# OpenSourceLights_v17.net
KiCad netlist of a schematic drawn in EAGLE
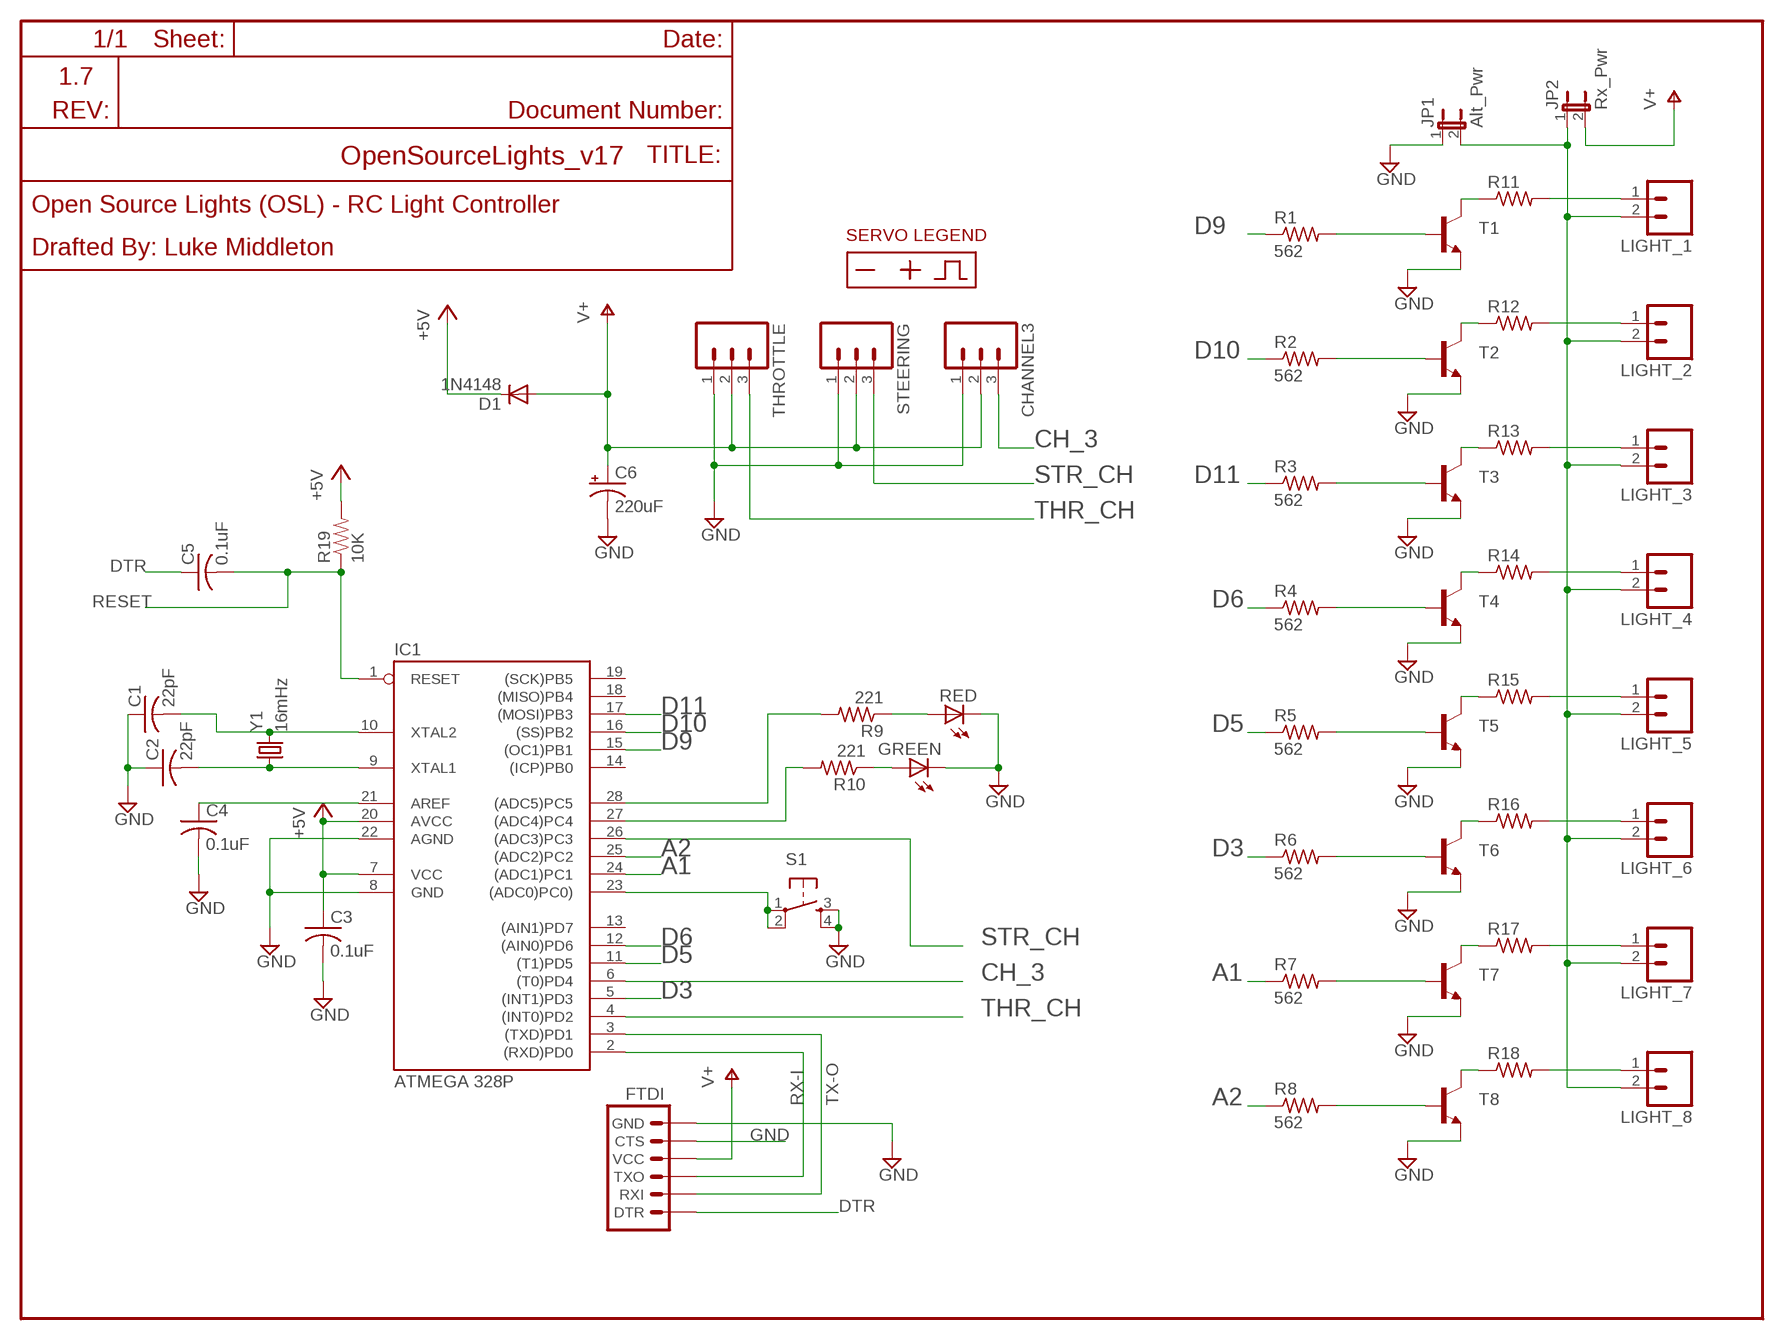
[diagram p0: schematic, sheet 1]

(export (version "E")
  (design (tool "Eeschema 10.0.6"))
  (components
    (comp (ref "C1")
      (value "22pF")
      (footprint "eagle-import:C025-025X050")
      (libsource (lib "eagle-import") (part "CAPACITORSMALL_THROUGH_HOLE"))
    )
    (comp (ref "C2")
      (value "22pF")
      (footprint "eagle-import:C025-025X050")
      (libsource (lib "eagle-import") (part "CAPACITORSMALL_THROUGH_HOLE"))
    )
    (comp (ref "C3")
      (value "0.1uF")
      (footprint "eagle-import:C025-025X050")
      (libsource (lib "eagle-import") (part "CAPACITORSMALL_THROUGH_HOLE"))
    )
    (comp (ref "C4")
      (value "0.1uF")
      (footprint "eagle-import:C025-025X050")
      (libsource (lib "eagle-import") (part "CAPACITORSMALL_THROUGH_HOLE"))
    )
    (comp (ref "C5")
      (value "0.1uF")
      (footprint "eagle-import:C025-025X050")
      (libsource (lib "eagle-import") (part "CAPACITORSMALL_THROUGH_HOLE"))
    )
    (comp (ref "C6")
      (value "220uF")
      (footprint "eagle-import:E5-10,5")
      (libsource (lib "eagle-import") (part "CPOL-USE5-10.5"))
    )
    (comp (ref "CHANNEL3")
      (value "M03LOCK")
      (footprint "eagle-import:1X03_LOCK")
      (libsource (lib "eagle-import") (part "M03LOCK"))
    )
    (comp (ref "D1")
      (value "1N4148")
      (footprint "eagle-import:DO35-10")
      (libsource (lib "eagle-import") (part "1N4148DO35-10"))
    )
    (comp (ref "FTDI")
      (value "ARDUINO_SERIAL_PROGRAMLOCK")
      (footprint "eagle-import:1X06_LOCK")
      (libsource (lib "eagle-import") (part "ARDUINO_SERIAL_PROGRAMLOCK"))
    )
    (comp (ref "GREEN")
      (value "LED3MM")
      (footprint "eagle-import:LED3MM")
      (libsource (lib "eagle-import") (part "LED3MM"))
    )
    (comp (ref "IC1")
      (value "ATMEGA 328P")
      (footprint "eagle-import:DIL28-3")
      (libsource (lib "eagle-import") (part "AT90S4433P"))
    )
    (comp (ref "JP1")
      (value "Alt_Pwr")
      (footprint "eagle-import:1X02")
      (libsource (lib "eagle-import") (part "JUMPER-2PTH"))
    )
    (comp (ref "JP2")
      (value "Rx_Pwr")
      (footprint "eagle-import:SJ_2S-NO")
      (libsource (lib "eagle-import") (part "JUMPER-2SMD-NO"))
    )
    (comp (ref "LIGHT_1")
      (value "M02JST-PTH-2_LARGEDRILL")
      (footprint "eagle-import:JST-2-PTH+")
      (libsource (lib "eagle-import") (part "M02JST-PTH-2_LARGEDRILL"))
    )
    (comp (ref "LIGHT_2")
      (value "M02JST-PTH-2_LARGEDRILL")
      (footprint "eagle-import:JST-2-PTH+")
      (libsource (lib "eagle-import") (part "M02JST-PTH-2_LARGEDRILL"))
    )
    (comp (ref "LIGHT_3")
      (value "M02JST-PTH-2_LARGEDRILL")
      (footprint "eagle-import:JST-2-PTH+")
      (libsource (lib "eagle-import") (part "M02JST-PTH-2_LARGEDRILL"))
    )
    (comp (ref "LIGHT_4")
      (value "M02JST-PTH-2_LARGEDRILL")
      (footprint "eagle-import:JST-2-PTH+")
      (libsource (lib "eagle-import") (part "M02JST-PTH-2_LARGEDRILL"))
    )
    (comp (ref "LIGHT_5")
      (value "M02JST-PTH-2_LARGEDRILL")
      (footprint "eagle-import:JST-2-PTH+")
      (libsource (lib "eagle-import") (part "M02JST-PTH-2_LARGEDRILL"))
    )
    (comp (ref "LIGHT_6")
      (value "M02JST-PTH-2_LARGEDRILL")
      (footprint "eagle-import:JST-2-PTH+")
      (libsource (lib "eagle-import") (part "M02JST-PTH-2_LARGEDRILL"))
    )
    (comp (ref "LIGHT_7")
      (value "M02JST-PTH-2_LARGEDRILL")
      (footprint "eagle-import:JST-2-PTH+")
      (libsource (lib "eagle-import") (part "M02JST-PTH-2_LARGEDRILL"))
    )
    (comp (ref "LIGHT_8")
      (value "M02JST-PTH-2_LARGEDRILL")
      (footprint "eagle-import:JST-2-PTH+")
      (libsource (lib "eagle-import") (part "M02JST-PTH-2_LARGEDRILL"))
    )
    (comp (ref "R1")
      (value "562")
      (footprint "eagle-import:RESISTOR_VERTICAL")
      (libsource (lib "eagle-import") (part "RESISTOR"))
    )
    (comp (ref "R2")
      (value "562")
      (footprint "eagle-import:RESISTOR_VERTICAL")
      (libsource (lib "eagle-import") (part "RESISTOR"))
    )
    (comp (ref "R3")
      (value "562")
      (footprint "eagle-import:RESISTOR_VERTICAL")
      (libsource (lib "eagle-import") (part "RESISTOR"))
    )
    (comp (ref "R4")
      (value "562")
      (footprint "eagle-import:RESISTOR_VERTICAL")
      (libsource (lib "eagle-import") (part "RESISTOR"))
    )
    (comp (ref "R5")
      (value "562")
      (footprint "eagle-import:RESISTOR_VERTICAL")
      (libsource (lib "eagle-import") (part "RESISTOR"))
    )
    (comp (ref "R6")
      (value "562")
      (footprint "eagle-import:RESISTOR_VERTICAL")
      (libsource (lib "eagle-import") (part "RESISTOR"))
    )
    (comp (ref "R7")
      (value "562")
      (footprint "eagle-import:RESISTOR_VERTICAL")
      (libsource (lib "eagle-import") (part "RESISTOR"))
    )
    (comp (ref "R8")
      (value "562")
      (footprint "eagle-import:RESISTOR_VERTICAL")
      (libsource (lib "eagle-import") (part "RESISTOR"))
    )
    (comp (ref "R9")
      (value "221")
      (footprint "eagle-import:RESISTOR_VERTICAL")
      (libsource (lib "eagle-import") (part "RESISTOR"))
    )
    (comp (ref "R10")
      (value "221")
      (footprint "eagle-import:RESISTOR_VERTICAL")
      (libsource (lib "eagle-import") (part "RESISTOR"))
    )
    (comp (ref "R11")
      (value "RESISTOR")
      (footprint "eagle-import:RESISTOR_VERTICAL")
      (libsource (lib "eagle-import") (part "RESISTOR"))
    )
    (comp (ref "R12")
      (value "RESISTOR")
      (footprint "eagle-import:RESISTOR_VERTICAL")
      (libsource (lib "eagle-import") (part "RESISTOR"))
    )
    (comp (ref "R13")
      (value "RESISTOR")
      (footprint "eagle-import:RESISTOR_VERTICAL")
      (libsource (lib "eagle-import") (part "RESISTOR"))
    )
    (comp (ref "R14")
      (value "RESISTOR")
      (footprint "eagle-import:RESISTOR_VERTICAL")
      (libsource (lib "eagle-import") (part "RESISTOR"))
    )
    (comp (ref "R15")
      (value "RESISTOR")
      (footprint "eagle-import:RESISTOR_VERTICAL")
      (libsource (lib "eagle-import") (part "RESISTOR"))
    )
    (comp (ref "R16")
      (value "RESISTOR")
      (footprint "eagle-import:RESISTOR_VERTICAL")
      (libsource (lib "eagle-import") (part "RESISTOR"))
    )
    (comp (ref "R17")
      (value "RESISTOR")
      (footprint "eagle-import:RESISTOR_VERTICAL")
      (libsource (lib "eagle-import") (part "RESISTOR"))
    )
    (comp (ref "R18")
      (value "RESISTOR")
      (footprint "eagle-import:RESISTOR_VERTICAL")
      (libsource (lib "eagle-import") (part "RESISTOR"))
    )
    (comp (ref "R19")
      (value "10K")
      (footprint "eagle-import:AXIAL-0.4")
      (libsource (lib "eagle-import") (part "RESISTORPTH-1/4W"))
    )
    (comp (ref "RED")
      (value "LED3MM")
      (footprint "eagle-import:LED3MM")
      (libsource (lib "eagle-import") (part "LED3MM"))
    )
    (comp (ref "S1")
      (value "TAC_SWITCHPTH")
      (footprint "eagle-import:TACTILE-PTH")
      (libsource (lib "eagle-import") (part "TAC_SWITCHPTH"))
    )
    (comp (ref "STEERING")
      (value "M03LOCK")
      (footprint "eagle-import:1X03_LOCK")
      (libsource (lib "eagle-import") (part "M03LOCK"))
    )
    (comp (ref "T1")
      (value "TRANSISTOR_NPNTH")
      (footprint "eagle-import:TO92")
      (libsource (lib "eagle-import") (part "TRANSISTOR_NPNTH"))
    )
    (comp (ref "T2")
      (value "TRANSISTOR_NPNTH")
      (footprint "eagle-import:TO92")
      (libsource (lib "eagle-import") (part "TRANSISTOR_NPNTH"))
    )
    (comp (ref "T3")
      (value "TRANSISTOR_NPNTH")
      (footprint "eagle-import:TO92")
      (libsource (lib "eagle-import") (part "TRANSISTOR_NPNTH"))
    )
    (comp (ref "T4")
      (value "TRANSISTOR_NPNTH")
      (footprint "eagle-import:TO92")
      (libsource (lib "eagle-import") (part "TRANSISTOR_NPNTH"))
    )
    (comp (ref "T5")
      (value "TRANSISTOR_NPNTH")
      (footprint "eagle-import:TO92")
      (libsource (lib "eagle-import") (part "TRANSISTOR_NPNTH"))
    )
    (comp (ref "T6")
      (value "TRANSISTOR_NPNTH")
      (footprint "eagle-import:TO92")
      (libsource (lib "eagle-import") (part "TRANSISTOR_NPNTH"))
    )
    (comp (ref "T7")
      (value "TRANSISTOR_NPNTH")
      (footprint "eagle-import:TO92")
      (libsource (lib "eagle-import") (part "TRANSISTOR_NPNTH"))
    )
    (comp (ref "T8")
      (value "TRANSISTOR_NPNTH")
      (footprint "eagle-import:TO92")
      (libsource (lib "eagle-import") (part "TRANSISTOR_NPNTH"))
    )
    (comp (ref "THROTTLE")
      (value "M03LOCK")
      (footprint "eagle-import:1X03_LOCK")
      (libsource (lib "eagle-import") (part "M03LOCK"))
    )
    (comp (ref "U$1")
      (value "SYMBOLS_SERVONEG_POS_SIG")
      (footprint "eagle-import:SYMBOLS_SERVO_REVERSE")
      (libsource (lib "eagle-import") (part "SYMBOLS_SERVONEG_POS_SIG"))
    )
    (comp (ref "Y1")
      (value "16mHz")
      (footprint "eagle-import:HC49US")
      (libsource (lib "eagle-import") (part "CRYSTALHC49US"))
    )
  )
  (nets
    (net (code "1") (name "+5V") (class "Default")
      (node (ref "C3") (pin "1") (pinfunction "1_1") (pintype "passive"))
      (node (ref "D1") (pin "C") (pinfunction "C_C") (pintype "passive"))
      (node (ref "IC1") (pin "20") (pinfunction "AVCC_20") (pintype "power_in"))
      (node (ref "IC1") (pin "7") (pinfunction "VCC_7") (pintype "power_in"))
      (node (ref "R19") (pin "P$2") (pinfunction "2_P$2") (pintype "passive"))
    )
    (net (code "2") (name "/A1") (class "Default")
      (node (ref "IC1") (pin "24") (pinfunction "(ADC1)PC1_24") (pintype "bidirectional"))
      (node (ref "R7") (pin "1") (pinfunction "1_1") (pintype "passive"))
    )
    (net (code "3") (name "/A2") (class "Default")
      (node (ref "IC1") (pin "25") (pinfunction "(ADC2)PC2_25") (pintype "bidirectional"))
      (node (ref "R8") (pin "1") (pinfunction "1_1") (pintype "passive"))
    )
    (net (code "4") (name "/CH_3") (class "Default")
      (node (ref "CHANNEL3") (pin "3") (pinfunction "3_3") (pintype "passive"))
      (node (ref "IC1") (pin "6") (pinfunction "(T0)PD4_6") (pintype "bidirectional"))
    )
    (net (code "5") (name "/D3") (class "Default")
      (node (ref "IC1") (pin "5") (pinfunction "(INT1)PD3_5") (pintype "bidirectional"))
      (node (ref "R6") (pin "1") (pinfunction "1_1") (pintype "passive"))
    )
    (net (code "6") (name "/D5") (class "Default")
      (node (ref "IC1") (pin "11") (pinfunction "(T1)PD5_11") (pintype "bidirectional"))
      (node (ref "R5") (pin "1") (pinfunction "1_1") (pintype "passive"))
    )
    (net (code "7") (name "/D6") (class "Default")
      (node (ref "IC1") (pin "12") (pinfunction "(AIN0)PD6_12") (pintype "bidirectional"))
      (node (ref "R4") (pin "1") (pinfunction "1_1") (pintype "passive"))
    )
    (net (code "8") (name "/D9") (class "Default")
      (node (ref "IC1") (pin "15") (pinfunction "(OC1)PB1_15") (pintype "bidirectional"))
      (node (ref "R1") (pin "1") (pinfunction "1_1") (pintype "passive"))
    )
    (net (code "9") (name "/D10") (class "Default")
      (node (ref "IC1") (pin "16") (pinfunction "(SS)PB2_16") (pintype "bidirectional"))
      (node (ref "R2") (pin "1") (pinfunction "1_1") (pintype "passive"))
    )
    (net (code "10") (name "/D11") (class "Default")
      (node (ref "IC1") (pin "17") (pinfunction "(MOSI)PB3_17") (pintype "bidirectional"))
      (node (ref "R3") (pin "1") (pinfunction "1_1") (pintype "passive"))
    )
    (net (code "11") (name "/DTR") (class "Default")
      (node (ref "C5") (pin "1") (pinfunction "1_1") (pintype "passive"))
      (node (ref "FTDI") (pin "1") (pinfunction "DTR_1") (pintype "passive"))
    )
    (net (code "12") (name "/RESET") (class "Default")
      (node (ref "C5") (pin "2") (pinfunction "2_2") (pintype "passive"))
      (node (ref "IC1") (pin "1") (pinfunction "RESET_1") (pintype "input"))
      (node (ref "R19") (pin "P$1") (pinfunction "1_P$1") (pintype "passive"))
    )
    (net (code "13") (name "/RX-I") (class "Default")
      (node (ref "FTDI") (pin "3") (pinfunction "TXO_3") (pintype "passive"))
      (node (ref "IC1") (pin "2") (pinfunction "(RXD)PD0_2") (pintype "bidirectional"))
    )
    (net (code "14") (name "/STR_CH") (class "Default")
      (node (ref "IC1") (pin "26") (pinfunction "(ADC3)PC3_26") (pintype "bidirectional"))
      (node (ref "STEERING") (pin "3") (pinfunction "3_3") (pintype "passive"))
    )
    (net (code "15") (name "/THR_CH") (class "Default")
      (node (ref "IC1") (pin "4") (pinfunction "(INT0)PD2_4") (pintype "bidirectional"))
      (node (ref "THROTTLE") (pin "3") (pinfunction "3_3") (pintype "passive"))
    )
    (net (code "16") (name "/TX-O") (class "Default")
      (node (ref "FTDI") (pin "2") (pinfunction "RXI_2") (pintype "passive"))
      (node (ref "IC1") (pin "3") (pinfunction "(TXD)PD1_3") (pintype "bidirectional"))
    )
    (net (code "17") (name "GND") (class "Default")
      (node (ref "C1") (pin "1") (pinfunction "1_1") (pintype "passive"))
      (node (ref "C2") (pin "1") (pinfunction "1_1") (pintype "passive"))
      (node (ref "C3") (pin "2") (pinfunction "2_2") (pintype "passive"))
      (node (ref "C4") (pin "2") (pinfunction "2_2") (pintype "passive"))
      (node (ref "C6") (pin "-") (pinfunction "-_-") (pintype "passive"))
      (node (ref "CHANNEL3") (pin "1") (pinfunction "1_1") (pintype "passive"))
      (node (ref "FTDI") (pin "5") (pinfunction "CTS_5") (pintype "passive"))
      (node (ref "FTDI") (pin "6") (pinfunction "GND_6") (pintype "passive"))
      (node (ref "GREEN") (pin "K") (pinfunction "C_K") (pintype "passive"))
      (node (ref "IC1") (pin "22") (pinfunction "AGND_22") (pintype "power_in"))
      (node (ref "IC1") (pin "8") (pinfunction "GND_8") (pintype "power_in"))
      (node (ref "JP1") (pin "1") (pinfunction "1_1") (pintype "passive"))
      (node (ref "RED") (pin "K") (pinfunction "C_K") (pintype "passive"))
      (node (ref "S1") (pin "3") (pinfunction "3_3") (pintype "passive"))
      (node (ref "S1") (pin "4") (pinfunction "4_4") (pintype "passive"))
      (node (ref "STEERING") (pin "1") (pinfunction "1_1") (pintype "passive"))
      (node (ref "T1") (pin "3") (pinfunction "E_3") (pintype "passive"))
      (node (ref "T2") (pin "3") (pinfunction "E_3") (pintype "passive"))
      (node (ref "T3") (pin "3") (pinfunction "E_3") (pintype "passive"))
      (node (ref "T4") (pin "3") (pinfunction "E_3") (pintype "passive"))
      (node (ref "T5") (pin "3") (pinfunction "E_3") (pintype "passive"))
      (node (ref "T6") (pin "3") (pinfunction "E_3") (pintype "passive"))
      (node (ref "T7") (pin "3") (pinfunction "E_3") (pintype "passive"))
      (node (ref "T8") (pin "3") (pinfunction "E_3") (pintype "passive"))
      (node (ref "THROTTLE") (pin "1") (pinfunction "1_1") (pintype "passive"))
    )
    (net (code "18") (name "Net-(GREEN-PadA)") (class "Default")
      (node (ref "GREEN") (pin "A") (pinfunction "A_A") (pintype "passive"))
      (node (ref "R10") (pin "1") (pinfunction "1_1") (pintype "passive"))
    )
    (net (code "19") (name "Net-(IC1-(ADC0)PC0))") (class "Default")
      (node (ref "IC1") (pin "23") (pinfunction "(ADC0)PC0)_23") (pintype "bidirectional"))
      (node (ref "S1") (pin "1") (pinfunction "1_1") (pintype "passive"))
      (node (ref "S1") (pin "2") (pinfunction "2_2") (pintype "passive"))
    )
    (net (code "20") (name "Net-(IC1-(ADC4)PC4)") (class "Default")
      (node (ref "IC1") (pin "27") (pinfunction "(ADC4)PC4_27") (pintype "bidirectional"))
      (node (ref "R10") (pin "2") (pinfunction "2_2") (pintype "passive"))
    )
    (net (code "21") (name "Net-(IC1-(ADC5)PC5)") (class "Default")
      (node (ref "IC1") (pin "28") (pinfunction "(ADC5)PC5_28") (pintype "bidirectional"))
      (node (ref "R9") (pin "2") (pinfunction "2_2") (pintype "passive"))
    )
    (net (code "22") (name "Net-(IC1-AREF)") (class "Default")
      (node (ref "C4") (pin "1") (pinfunction "1_1") (pintype "passive"))
      (node (ref "IC1") (pin "21") (pinfunction "AREF_21") (pintype "passive"))
    )
    (net (code "23") (name "Net-(IC1-XTAL1)") (class "Default")
      (node (ref "C2") (pin "2") (pinfunction "2_2") (pintype "passive"))
      (node (ref "IC1") (pin "9") (pinfunction "XTAL1_9") (pintype "bidirectional"))
      (node (ref "Y1") (pin "1") (pinfunction "1_1") (pintype "passive"))
    )
    (net (code "24") (name "Net-(IC1-XTAL2)") (class "Default")
      (node (ref "C1") (pin "2") (pinfunction "2_2") (pintype "passive"))
      (node (ref "IC1") (pin "10") (pinfunction "XTAL2_10") (pintype "bidirectional"))
      (node (ref "Y1") (pin "2") (pinfunction "2_2") (pintype "passive"))
    )
    (net (code "25") (name "Net-(JP1-Pad2)") (class "Default")
      (node (ref "JP1") (pin "2") (pinfunction "2_2") (pintype "passive"))
      (node (ref "JP2") (pin "1") (pinfunction "1_1") (pintype "passive"))
      (node (ref "LIGHT_1") (pin "2") (pinfunction "2_2") (pintype "passive"))
      (node (ref "LIGHT_2") (pin "2") (pinfunction "2_2") (pintype "passive"))
      (node (ref "LIGHT_3") (pin "2") (pinfunction "2_2") (pintype "passive"))
      (node (ref "LIGHT_4") (pin "2") (pinfunction "2_2") (pintype "passive"))
      (node (ref "LIGHT_5") (pin "2") (pinfunction "2_2") (pintype "passive"))
      (node (ref "LIGHT_6") (pin "2") (pinfunction "2_2") (pintype "passive"))
      (node (ref "LIGHT_7") (pin "2") (pinfunction "2_2") (pintype "passive"))
      (node (ref "LIGHT_8") (pin "2") (pinfunction "2_2") (pintype "passive"))
    )
    (net (code "26") (name "Net-(LIGHT_1-Pad1)") (class "Default")
      (node (ref "LIGHT_1") (pin "1") (pinfunction "1_1") (pintype "passive"))
      (node (ref "R11") (pin "2") (pinfunction "2_2") (pintype "passive"))
    )
    (net (code "27") (name "Net-(LIGHT_2-Pad1)") (class "Default")
      (node (ref "LIGHT_2") (pin "1") (pinfunction "1_1") (pintype "passive"))
      (node (ref "R12") (pin "2") (pinfunction "2_2") (pintype "passive"))
    )
    (net (code "28") (name "Net-(LIGHT_3-Pad1)") (class "Default")
      (node (ref "LIGHT_3") (pin "1") (pinfunction "1_1") (pintype "passive"))
      (node (ref "R13") (pin "2") (pinfunction "2_2") (pintype "passive"))
    )
    (net (code "29") (name "Net-(LIGHT_4-Pad1)") (class "Default")
      (node (ref "LIGHT_4") (pin "1") (pinfunction "1_1") (pintype "passive"))
      (node (ref "R14") (pin "2") (pinfunction "2_2") (pintype "passive"))
    )
    (net (code "30") (name "Net-(LIGHT_5-Pad1)") (class "Default")
      (node (ref "LIGHT_5") (pin "1") (pinfunction "1_1") (pintype "passive"))
      (node (ref "R15") (pin "2") (pinfunction "2_2") (pintype "passive"))
    )
    (net (code "31") (name "Net-(LIGHT_6-Pad1)") (class "Default")
      (node (ref "LIGHT_6") (pin "1") (pinfunction "1_1") (pintype "passive"))
      (node (ref "R16") (pin "2") (pinfunction "2_2") (pintype "passive"))
    )
    (net (code "32") (name "Net-(LIGHT_7-Pad1)") (class "Default")
      (node (ref "LIGHT_7") (pin "1") (pinfunction "1_1") (pintype "passive"))
      (node (ref "R17") (pin "2") (pinfunction "2_2") (pintype "passive"))
    )
    (net (code "33") (name "Net-(LIGHT_8-Pad1)") (class "Default")
      (node (ref "LIGHT_8") (pin "1") (pinfunction "1_1") (pintype "passive"))
      (node (ref "R18") (pin "2") (pinfunction "2_2") (pintype "passive"))
    )
    (net (code "34") (name "Net-(R9-Pad1)") (class "Default")
      (node (ref "R9") (pin "1") (pinfunction "1_1") (pintype "passive"))
      (node (ref "RED") (pin "A") (pinfunction "A_A") (pintype "passive"))
    )
    (net (code "35") (name "Net-(T1-B)") (class "Default")
      (node (ref "R1") (pin "2") (pinfunction "2_2") (pintype "passive"))
      (node (ref "T1") (pin "2") (pinfunction "B_2") (pintype "passive"))
    )
    (net (code "36") (name "Net-(T1-C)") (class "Default")
      (node (ref "R11") (pin "1") (pinfunction "1_1") (pintype "passive"))
      (node (ref "T1") (pin "1") (pinfunction "C_1") (pintype "passive"))
    )
    (net (code "37") (name "Net-(T2-B)") (class "Default")
      (node (ref "R2") (pin "2") (pinfunction "2_2") (pintype "passive"))
      (node (ref "T2") (pin "2") (pinfunction "B_2") (pintype "passive"))
    )
    (net (code "38") (name "Net-(T2-C)") (class "Default")
      (node (ref "R12") (pin "1") (pinfunction "1_1") (pintype "passive"))
      (node (ref "T2") (pin "1") (pinfunction "C_1") (pintype "passive"))
    )
    (net (code "39") (name "Net-(T3-B)") (class "Default")
      (node (ref "R3") (pin "2") (pinfunction "2_2") (pintype "passive"))
      (node (ref "T3") (pin "2") (pinfunction "B_2") (pintype "passive"))
    )
    (net (code "40") (name "Net-(T3-C)") (class "Default")
      (node (ref "R13") (pin "1") (pinfunction "1_1") (pintype "passive"))
      (node (ref "T3") (pin "1") (pinfunction "C_1") (pintype "passive"))
    )
    (net (code "41") (name "Net-(T4-B)") (class "Default")
      (node (ref "R4") (pin "2") (pinfunction "2_2") (pintype "passive"))
      (node (ref "T4") (pin "2") (pinfunction "B_2") (pintype "passive"))
    )
    (net (code "42") (name "Net-(T4-C)") (class "Default")
      (node (ref "R14") (pin "1") (pinfunction "1_1") (pintype "passive"))
      (node (ref "T4") (pin "1") (pinfunction "C_1") (pintype "passive"))
    )
    (net (code "43") (name "Net-(T5-B)") (class "Default")
      (node (ref "R5") (pin "2") (pinfunction "2_2") (pintype "passive"))
      (node (ref "T5") (pin "2") (pinfunction "B_2") (pintype "passive"))
    )
    (net (code "44") (name "Net-(T5-C)") (class "Default")
      (node (ref "R15") (pin "1") (pinfunction "1_1") (pintype "passive"))
      (node (ref "T5") (pin "1") (pinfunction "C_1") (pintype "passive"))
    )
    (net (code "45") (name "Net-(T6-B)") (class "Default")
      (node (ref "R6") (pin "2") (pinfunction "2_2") (pintype "passive"))
      (node (ref "T6") (pin "2") (pinfunction "B_2") (pintype "passive"))
    )
    (net (code "46") (name "Net-(T6-C)") (class "Default")
      (node (ref "R16") (pin "1") (pinfunction "1_1") (pintype "passive"))
      (node (ref "T6") (pin "1") (pinfunction "C_1") (pintype "passive"))
    )
    (net (code "47") (name "Net-(T7-B)") (class "Default")
      (node (ref "R7") (pin "2") (pinfunction "2_2") (pintype "passive"))
      (node (ref "T7") (pin "2") (pinfunction "B_2") (pintype "passive"))
    )
    (net (code "48") (name "Net-(T7-C)") (class "Default")
      (node (ref "R17") (pin "1") (pinfunction "1_1") (pintype "passive"))
      (node (ref "T7") (pin "1") (pinfunction "C_1") (pintype "passive"))
    )
    (net (code "49") (name "Net-(T8-B)") (class "Default")
      (node (ref "R8") (pin "2") (pinfunction "2_2") (pintype "passive"))
      (node (ref "T8") (pin "2") (pinfunction "B_2") (pintype "passive"))
    )
    (net (code "50") (name "Net-(T8-C)") (class "Default")
      (node (ref "R18") (pin "1") (pinfunction "1_1") (pintype "passive"))
      (node (ref "T8") (pin "1") (pinfunction "C_1") (pintype "passive"))
    )
    (net (code "51") (name "V+") (class "Default")
      (node (ref "C6") (pin "+") (pinfunction "+_+") (pintype "passive"))
      (node (ref "CHANNEL3") (pin "2") (pinfunction "2_2") (pintype "passive"))
      (node (ref "D1") (pin "A") (pinfunction "A_A") (pintype "passive"))
      (node (ref "FTDI") (pin "4") (pinfunction "VCC_4") (pintype "passive"))
      (node (ref "JP2") (pin "2") (pinfunction "2_2") (pintype "passive"))
      (node (ref "STEERING") (pin "2") (pinfunction "2_2") (pintype "passive"))
      (node (ref "THROTTLE") (pin "2") (pinfunction "2_2") (pintype "passive"))
    )
    (net (code "52") (name "unconnected-(IC1-(AIN1)PD7-Pad13)") (class "Default")
      (node (ref "IC1") (pin "13") (pinfunction "(AIN1)PD7_13") (pintype "bidirectional"))
    )
    (net (code "53") (name "unconnected-(IC1-(ICP)PB0-Pad14)") (class "Default")
      (node (ref "IC1") (pin "14") (pinfunction "(ICP)PB0_14") (pintype "bidirectional"))
    )
    (net (code "54") (name "unconnected-(IC1-(MISO)PB4-Pad18)") (class "Default")
      (node (ref "IC1") (pin "18") (pinfunction "(MISO)PB4_18") (pintype "bidirectional"))
    )
    (net (code "55") (name "unconnected-(IC1-(SCK)PB5-Pad19)") (class "Default")
      (node (ref "IC1") (pin "19") (pinfunction "(SCK)PB5_19") (pintype "bidirectional"))
    )
  )
)
